# motordriver-v3_1_A3931.net
KiCad netlist of a schematic drawn in Altium Designer
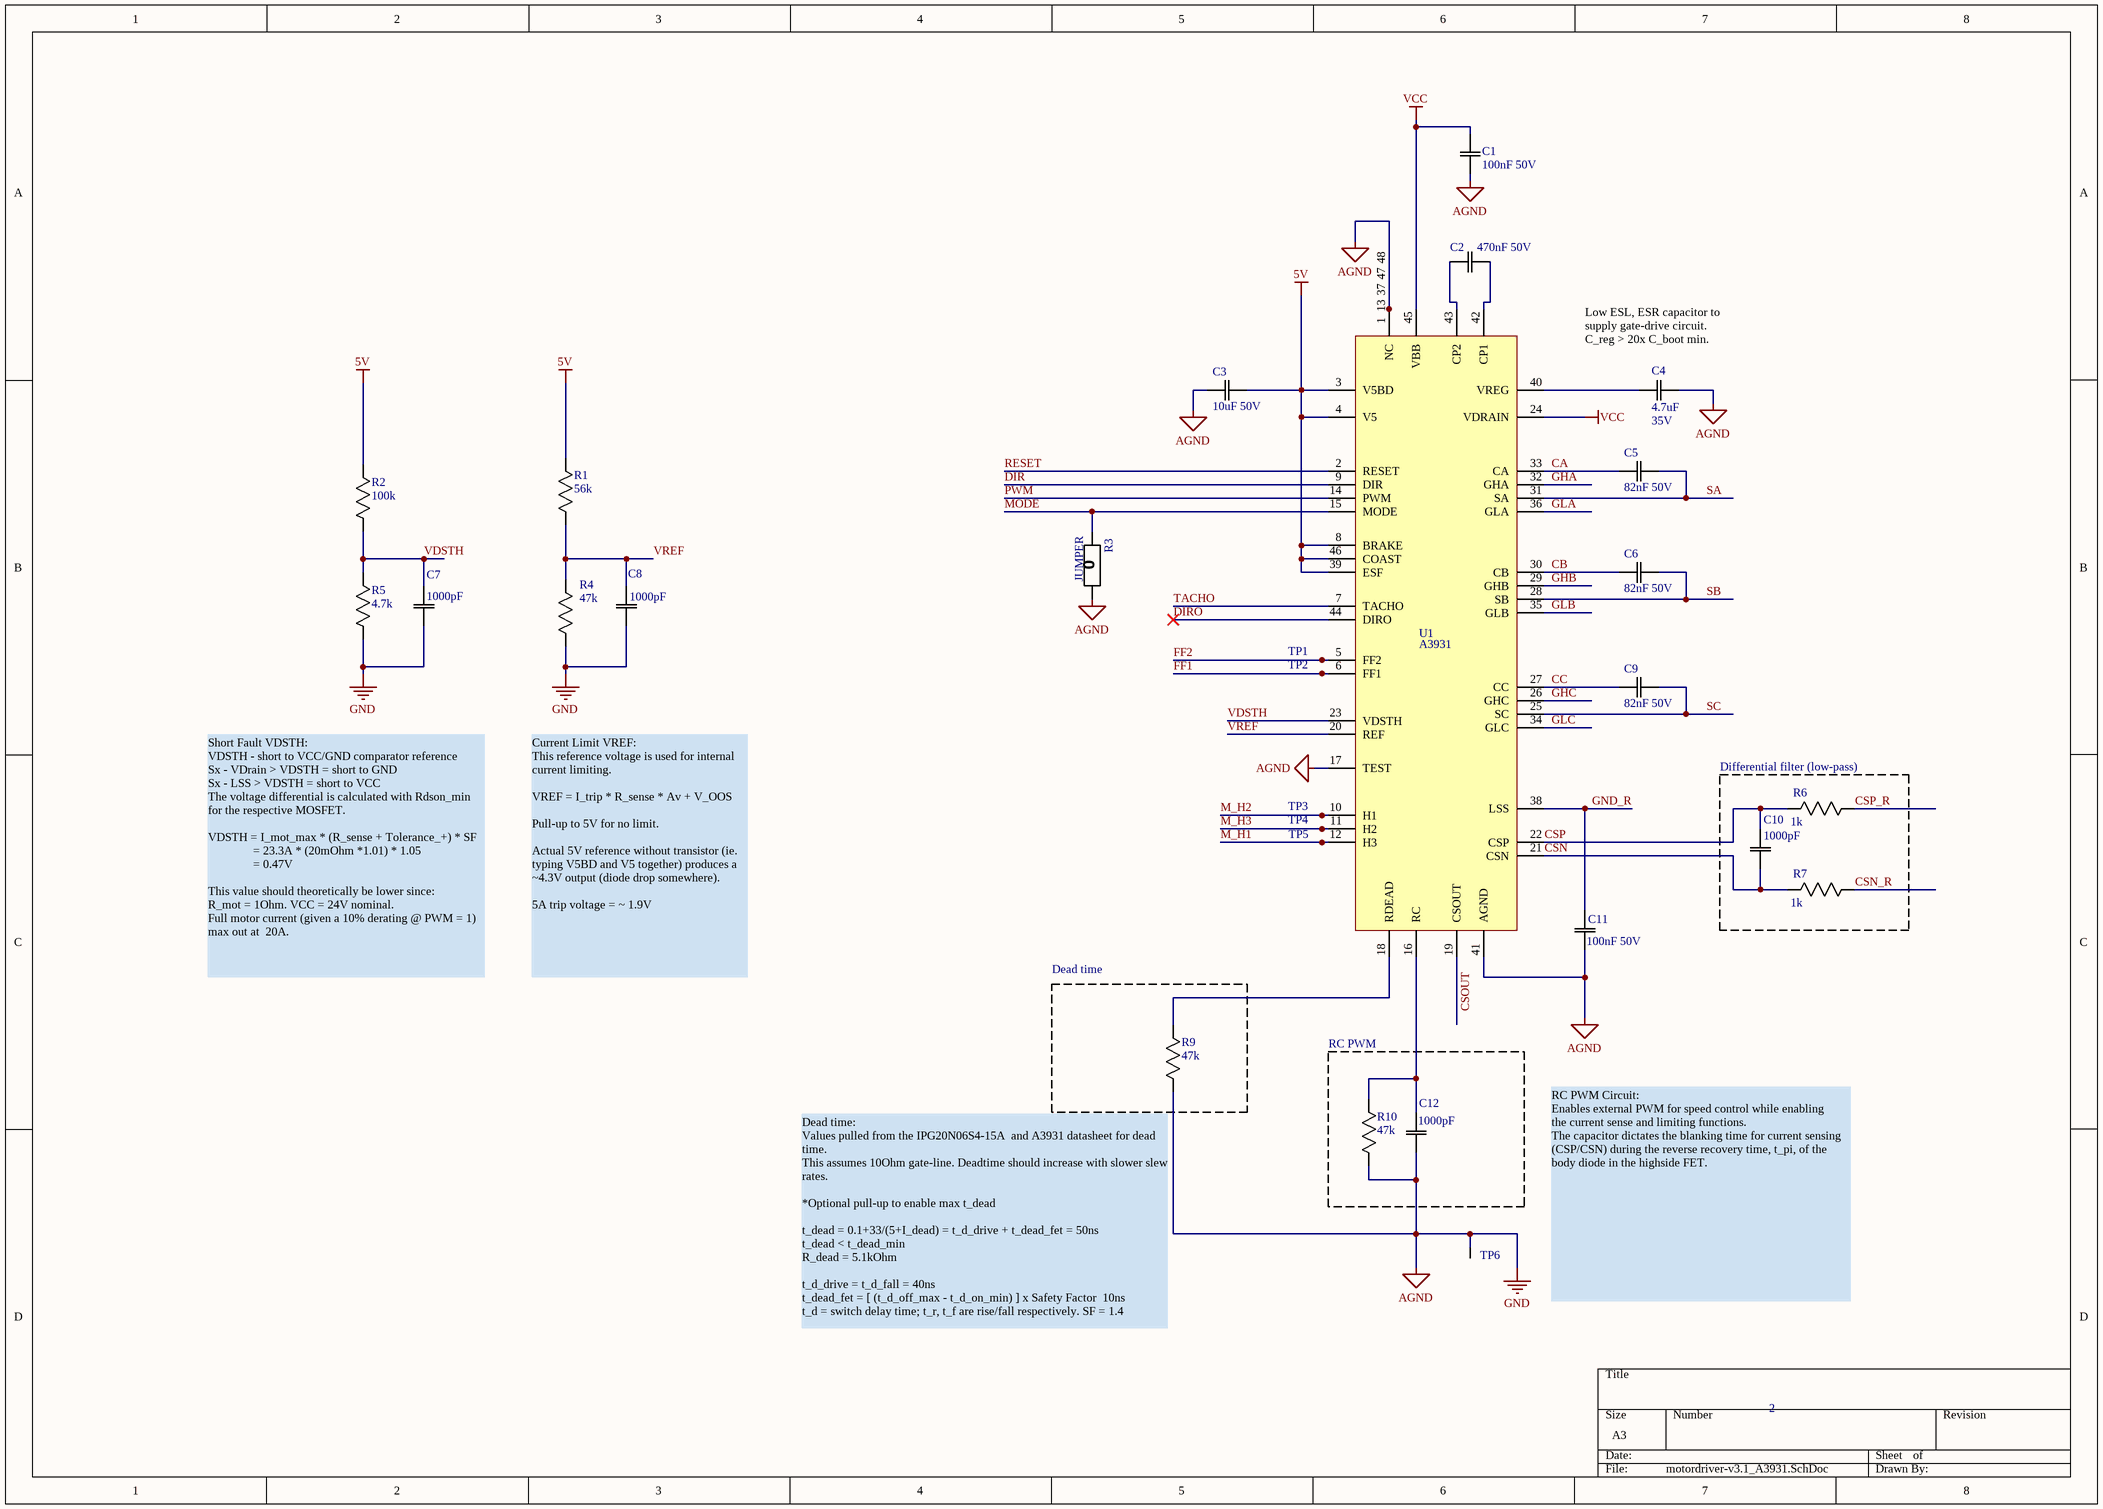
[diagram p0: motordriver-v3.1_A3931.SchDoc]

(export (version "E")
  (design (tool "Eeschema 10.0.6"))
  (components
    (comp (ref "C1")
      (value "100nF 50V")
      (footprint "0603")
      (description "CAP CER 0.1UF 50V X7R 0805")
      (fields (field (name "TOLERANCE") "10%"))
      (libsource (lib "AltiumLibraries") (part "CAP 100nF 50V"))
    )
    (comp (ref "C2")
      (value "470nF 50V")
      (footprint "0603")
      (description "CAP CER 0.1UF 50V X7R 0805")
      (fields (field (name "TOLERANCE") "10%"))
      (libsource (lib "AltiumLibraries") (part "CAP 470nF 50V"))
    )
    (comp (ref "C3")
      (value "10uF 50V")
      (footprint "0805")
      (description "CAP CER 10UF 50V X7R")
      (fields (field (name "TOLERANCE") "10%"))
      (libsource (lib "AltiumLibraries") (part "CAP 10uF 50V"))
    )
    (comp (ref "C4")
      (value "4.7uF")
      (footprint "0603")
      (description "CAP CER 4.7UF 35V X7R 0603/0805")
      (fields (field (name "TOLERANCE") "10%") (field (name "RATING") "35V"))
      (libsource (lib "AltiumLibraries") (part "CAP 4.7uF 35V"))
    )
    (comp (ref "C5")
      (value "82nF 50V")
      (footprint "0603")
      (description "CAP CER 0.082UF 50V X7R 0805")
      (fields (field (name "TOLERANCE") "5%"))
      (libsource (lib "AltiumLibraries") (part "CAP 82nF 50V"))
    )
    (comp (ref "C6")
      (value "82nF 50V")
      (footprint "0603")
      (description "CAP CER 0.082UF 50V X7R 0805")
      (fields (field (name "TOLERANCE") "5%"))
      (libsource (lib "AltiumLibraries") (part "CAP 82nF 50V"))
    )
    (comp (ref "C7")
      (value "1000pF")
      (footprint "0603")
      (description "CAP CER 1000PF 50V X7R 0603/0805")
      (fields (field (name "TOLERANCE") "10%"))
      (libsource (lib "AltiumLibraries") (part "CAP 1000pF 50V"))
    )
    (comp (ref "C8")
      (value "1000pF")
      (footprint "0603")
      (description "CAP CER 1000PF 50V X7R 0603/0805")
      (fields (field (name "TOLERANCE") "10%"))
      (libsource (lib "AltiumLibraries") (part "CAP 1000pF 50V"))
    )
    (comp (ref "C9")
      (value "82nF 50V")
      (footprint "0603")
      (description "CAP CER 0.082UF 50V X7R 0805")
      (fields (field (name "TOLERANCE") "5%"))
      (libsource (lib "AltiumLibraries") (part "CAP 82nF 50V"))
    )
    (comp (ref "C10")
      (value "1000pF")
      (footprint "0603")
      (description "CAP CER 1000PF 50V X7R 0603/0805")
      (fields (field (name "TOLERANCE") "10%"))
      (libsource (lib "AltiumLibraries") (part "CAP 1000pF 50V"))
    )
    (comp (ref "C11")
      (value "100nF 50V")
      (footprint "0603")
      (description "CAP CER 0.1UF 50V X7R 0805")
      (fields (field (name "TOLERANCE") "10%"))
      (libsource (lib "AltiumLibraries") (part "CAP 100nF 50V"))
    )
    (comp (ref "C12")
      (value "1000pF")
      (footprint "0603")
      (description "CAP CER 1000PF 50V X7R 0603/0805")
      (fields (field (name "TOLERANCE") "10%"))
      (libsource (lib "AltiumLibraries") (part "CAP 1000pF 50V"))
    )
    (comp (ref "R1")
      (value "56k")
      (footprint "0603")
      (description "RES SMD 100K OHM 1% 1/8W 0805")
      (fields (field (name "TOLERANCE") "1%"))
      (libsource (lib "") (part "RES 100k 1/8W - 1%_1"))
    )
    (comp (ref "R2")
      (value "100k")
      (footprint "0603")
      (description "RES SMD 100K OHM 1% 1/8W 0805")
      (fields (field (name "TOLERANCE") "1%"))
      (libsource (lib "AltiumLibraries") (part "RES 100k 1/8W - 1%"))
    )
    (comp (ref "R3")
      (value "JUMPER")
      (footprint "0603")
      (description "RES SMD 0 OHM JUMPER GENERIC 0805")
      (libsource (lib "AltiumLibraries") (part "RES 0 JUMPER"))
    )
    (comp (ref "R4")
      (value "47k")
      (footprint "0603")
      (description "RES SMD 47K OHM 1% 1/8W 0805")
      (fields (field (name "TOLERANCE") "1%"))
      (libsource (lib "AltiumLibraries") (part "RES 47k 1/8W - 1%"))
    )
    (comp (ref "R5")
      (value "4.7k")
      (footprint "0603")
      (description "RES SMD 4.7k OHM 1% 1/8W 0805")
      (fields (field (name "TOLERANCE") "1%"))
      (libsource (lib "AltiumLibraries") (part "RES 4.7k 1/8W - 1%"))
    )
    (comp (ref "R6")
      (value "1k")
      (footprint "0603")
      (description "RES SMD 1K OHM 5% 1/8W 0805")
      (fields (field (name "TOLERANCE") "5%"))
      (libsource (lib "AltiumLibraries") (part "RES 1k 1/8W"))
    )
    (comp (ref "R7")
      (value "1k")
      (footprint "0603")
      (description "RES SMD 1K OHM 5% 1/8W 0805")
      (fields (field (name "TOLERANCE") "5%"))
      (libsource (lib "AltiumLibraries") (part "RES 1k 1/8W"))
    )
    (comp (ref "R9")
      (value "47k")
      (footprint "0603")
      (description "RES SMD 5.1K OHM 1% 1/8W 0805")
      (fields (field (name "TOLERANCE") "1%"))
      (libsource (lib "AltiumLibraries") (part "RES 5.1k 1/8W - 1%"))
    )
    (comp (ref "R10")
      (value "47k")
      (footprint "0603")
      (description "RES SMD 47K OHM 1% 1/8W 0805")
      (fields (field (name "TOLERANCE") "1%"))
      (libsource (lib "") (part "RES 47k 1/8W - 1%_1"))
    )
    (comp (ref "TP1")
      (value "Test Point (Via)")
      (footprint "TP")
      (libsource (lib "AltiumLibraries") (part "Test Point (Via)"))
    )
    (comp (ref "TP2")
      (value "Test Point (Via)")
      (footprint "TP")
      (libsource (lib "AltiumLibraries") (part "Test Point (Via)"))
    )
    (comp (ref "TP3")
      (value "Test Point (Via)")
      (footprint "TP")
      (libsource (lib "AltiumLibraries") (part "Test Point (Via)"))
    )
    (comp (ref "TP4")
      (value "Test Point (Via)")
      (footprint "TP")
      (libsource (lib "AltiumLibraries") (part "Test Point (Via)"))
    )
    (comp (ref "TP5")
      (value "Test Point (Via)")
      (footprint "TP")
      (libsource (lib "AltiumLibraries") (part "Test Point (Via)"))
    )
    (comp (ref "TP6")
      (value "Test Point (Via)")
      (footprint "TP")
      (libsource (lib "AltiumLibraries") (part "Test Point (Via)"))
    )
    (comp (ref "U1")
      (value "A3931")
      (footprint "48-LQFP-EP (7x7)")
      (description "IC MOTOR DRIVER 5.5V-50V 48LQFP - Alternative Symbol")
      (libsource (lib "AltiumLibraries") (part "A3931_A1"))
    )
  )
  (nets
    (net (code "1") (name "/CA") (class "Default")
      (node (ref "C5") (pin "1") (pinfunction "C1_1") (pintype "passive"))
      (node (ref "U1") (pin "33") (pinfunction "CA_33") (pintype "passive"))
    )
    (net (code "2") (name "/CB") (class "Default")
      (node (ref "C6") (pin "1") (pinfunction "C1_1") (pintype "passive"))
      (node (ref "U1") (pin "30") (pinfunction "CB_30") (pintype "passive"))
    )
    (net (code "3") (name "/CC") (class "Default")
      (node (ref "C9") (pin "1") (pinfunction "C1_1") (pintype "passive"))
      (node (ref "U1") (pin "27") (pinfunction "CC_27") (pintype "passive"))
    )
    (net (code "4") (name "/CSN") (class "Default")
      (node (ref "C10") (pin "1") (pinfunction "C1_1") (pintype "passive"))
      (node (ref "R7") (pin "2") (pinfunction "R2_2") (pintype "passive"))
      (node (ref "U1") (pin "21") (pinfunction "CSN_21") (pintype "passive"))
    )
    (net (code "5") (name "/CSN_R") (class "Default")
      (node (ref "R7") (pin "1") (pinfunction "R1_1") (pintype "passive"))
    )
    (net (code "6") (name "/CSOUT") (class "Default")
      (node (ref "U1") (pin "19") (pinfunction "CSOUT_19") (pintype "passive"))
    )
    (net (code "7") (name "/CSP") (class "Default")
      (node (ref "C10") (pin "2") (pinfunction "C2_2") (pintype "passive"))
      (node (ref "R6") (pin "2") (pinfunction "R2_2") (pintype "passive"))
      (node (ref "U1") (pin "22") (pinfunction "CSP_22") (pintype "passive"))
    )
    (net (code "8") (name "/CSP_R") (class "Default")
      (node (ref "R6") (pin "1") (pinfunction "R1_1") (pintype "passive"))
    )
    (net (code "9") (name "/DIR") (class "Default")
      (node (ref "U1") (pin "9") (pinfunction "DIR_9") (pintype "passive"))
    )
    (net (code "10") (name "/DIRO") (class "Default")
      (node (ref "U1") (pin "44") (pinfunction "DIRO_44") (pintype "passive+no_connect"))
    )
    (net (code "11") (name "/FF1") (class "Default")
      (node (ref "TP2") (pin "1") (pinfunction "1_1") (pintype "passive"))
      (node (ref "U1") (pin "6") (pinfunction "FF1_6") (pintype "passive"))
    )
    (net (code "12") (name "/FF2") (class "Default")
      (node (ref "TP1") (pin "1") (pinfunction "1_1") (pintype "passive"))
      (node (ref "U1") (pin "5") (pinfunction "FF2_5") (pintype "passive"))
    )
    (net (code "13") (name "/GHA") (class "Default")
      (node (ref "U1") (pin "32") (pinfunction "GHA_32") (pintype "passive"))
    )
    (net (code "14") (name "/GHB") (class "Default")
      (node (ref "U1") (pin "29") (pinfunction "GHB_29") (pintype "passive"))
    )
    (net (code "15") (name "/GHC") (class "Default")
      (node (ref "U1") (pin "26") (pinfunction "GHC_26") (pintype "passive"))
    )
    (net (code "16") (name "/GLA") (class "Default")
      (node (ref "U1") (pin "36") (pinfunction "GLA_36") (pintype "passive"))
    )
    (net (code "17") (name "/GLB") (class "Default")
      (node (ref "U1") (pin "35") (pinfunction "GLB_35") (pintype "passive"))
    )
    (net (code "18") (name "/GLC") (class "Default")
      (node (ref "U1") (pin "34") (pinfunction "GLC_34") (pintype "passive"))
    )
    (net (code "19") (name "/GND_R") (class "Default")
      (node (ref "C11") (pin "2") (pinfunction "C2_2") (pintype "passive"))
      (node (ref "U1") (pin "38") (pinfunction "LSS_38") (pintype "passive"))
    )
    (net (code "20") (name "/MODE") (class "Default")
      (node (ref "R3") (pin "2") (pinfunction "R2_2") (pintype "passive"))
      (node (ref "U1") (pin "15") (pinfunction "MODE_15") (pintype "passive"))
    )
    (net (code "21") (name "/M_H1") (class "Default")
      (node (ref "TP5") (pin "1") (pinfunction "1_1") (pintype "passive"))
      (node (ref "U1") (pin "12") (pinfunction "H3_12") (pintype "passive"))
    )
    (net (code "22") (name "/M_H2") (class "Default")
      (node (ref "TP3") (pin "1") (pinfunction "1_1") (pintype "passive"))
      (node (ref "U1") (pin "10") (pinfunction "H1_10") (pintype "passive"))
    )
    (net (code "23") (name "/M_H3") (class "Default")
      (node (ref "TP4") (pin "1") (pinfunction "1_1") (pintype "passive"))
      (node (ref "U1") (pin "11") (pinfunction "H2_11") (pintype "passive"))
    )
    (net (code "24") (name "/PWM") (class "Default")
      (node (ref "U1") (pin "14") (pinfunction "PWM_14") (pintype "passive"))
    )
    (net (code "25") (name "/RESET") (class "Default")
      (node (ref "U1") (pin "2") (pinfunction "RESET_2") (pintype "passive"))
    )
    (net (code "26") (name "/SA") (class "Default")
      (node (ref "C5") (pin "2") (pinfunction "C2_2") (pintype "passive"))
      (node (ref "U1") (pin "31") (pinfunction "SA_31") (pintype "passive"))
    )
    (net (code "27") (name "/SB") (class "Default")
      (node (ref "C6") (pin "2") (pinfunction "C2_2") (pintype "passive"))
      (node (ref "U1") (pin "28") (pinfunction "SB_28") (pintype "passive"))
    )
    (net (code "28") (name "/SC") (class "Default")
      (node (ref "C9") (pin "2") (pinfunction "C2_2") (pintype "passive"))
      (node (ref "U1") (pin "25") (pinfunction "SC_25") (pintype "passive"))
    )
    (net (code "29") (name "/TACHO") (class "Default")
      (node (ref "U1") (pin "7") (pinfunction "TACHO_7") (pintype "passive"))
    )
    (net (code "30") (name "/VDSTH") (class "Default")
      (node (ref "C7") (pin "2") (pinfunction "C2_2") (pintype "passive"))
      (node (ref "R2") (pin "2") (pinfunction "R2_2") (pintype "passive"))
      (node (ref "R5") (pin "1") (pinfunction "R1_1") (pintype "passive"))
      (node (ref "U1") (pin "23") (pinfunction "VDSTH_23") (pintype "passive"))
    )
    (net (code "31") (name "/VREF") (class "Default")
      (node (ref "C8") (pin "2") (pinfunction "C2_2") (pintype "passive"))
      (node (ref "R1") (pin "2") (pinfunction "R2_2") (pintype "passive"))
      (node (ref "R4") (pin "2") (pinfunction "R2_2") (pintype "passive"))
      (node (ref "U1") (pin "20") (pinfunction "REF_20") (pintype "passive"))
    )
    (net (code "32") (name "5V") (class "Default")
      (node (ref "C3") (pin "2") (pinfunction "C2_2") (pintype "passive"))
      (node (ref "R1") (pin "1") (pinfunction "R1_1") (pintype "passive"))
      (node (ref "R2") (pin "1") (pinfunction "R1_1") (pintype "passive"))
      (node (ref "U1") (pin "3") (pinfunction "V5BD_3") (pintype "passive"))
      (node (ref "U1") (pin "39") (pinfunction "ESF_39") (pintype "passive"))
      (node (ref "U1") (pin "4") (pinfunction "V5_4") (pintype "passive"))
      (node (ref "U1") (pin "46") (pinfunction "COAST_46") (pintype "passive"))
      (node (ref "U1") (pin "8") (pinfunction "BRAKE_8") (pintype "passive"))
    )
    (net (code "33") (name "AGND") (class "Default")
      (node (ref "C1") (pin "1") (pinfunction "C1_1") (pintype "passive"))
      (node (ref "C11") (pin "1") (pinfunction "C1_1") (pintype "passive"))
      (node (ref "C12") (pin "1") (pinfunction "C1_1") (pintype "passive"))
      (node (ref "C3") (pin "1") (pinfunction "C1_1") (pintype "passive"))
      (node (ref "C4") (pin "2") (pinfunction "C2_2") (pintype "passive"))
      (node (ref "C7") (pin "1") (pinfunction "C1_1") (pintype "passive"))
      (node (ref "C8") (pin "1") (pinfunction "C1_1") (pintype "passive"))
      (node (ref "R10") (pin "2") (pinfunction "R2_2") (pintype "passive"))
      (node (ref "R3") (pin "1") (pinfunction "R1_1") (pintype "passive"))
      (node (ref "R4") (pin "1") (pinfunction "R1_1") (pintype "passive"))
      (node (ref "R5") (pin "2") (pinfunction "R2_2") (pintype "passive"))
      (node (ref "R9") (pin "2") (pinfunction "R2_2") (pintype "passive"))
      (node (ref "TP6") (pin "1") (pinfunction "1_1") (pintype "passive"))
      (node (ref "U1") (pin "1") (pinfunction "NC_1") (pintype "passive"))
      (node (ref "U1") (pin "13") (pinfunction "13_13") (pintype "passive"))
      (node (ref "U1") (pin "17") (pinfunction "TEST_17") (pintype "passive"))
      (node (ref "U1") (pin "37") (pinfunction "NC_37") (pintype "passive"))
      (node (ref "U1") (pin "41") (pinfunction "AGND_41") (pintype "passive"))
      (node (ref "U1") (pin "47") (pinfunction "NC_47") (pintype "passive"))
      (node (ref "U1") (pin "48") (pinfunction "NC_48") (pintype "passive"))
    )
    (net (code "34") (name "Net-(C2-C1)") (class "Default")
      (node (ref "C2") (pin "1") (pinfunction "C1_1") (pintype "passive"))
      (node (ref "U1") (pin "43") (pinfunction "CP2_43") (pintype "passive"))
    )
    (net (code "35") (name "Net-(C2-C2)") (class "Default")
      (node (ref "C2") (pin "2") (pinfunction "C2_2") (pintype "passive"))
      (node (ref "U1") (pin "42") (pinfunction "CP1_42") (pintype "passive"))
    )
    (net (code "36") (name "Net-(C4-C1)") (class "Default")
      (node (ref "C4") (pin "1") (pinfunction "C1_1") (pintype "passive"))
      (node (ref "U1") (pin "40") (pinfunction "VREG_40") (pintype "passive"))
    )
    (net (code "37") (name "Net-(C12-C2)") (class "Default")
      (node (ref "C12") (pin "2") (pinfunction "C2_2") (pintype "passive"))
      (node (ref "R10") (pin "1") (pinfunction "R1_1") (pintype "passive"))
      (node (ref "U1") (pin "16") (pinfunction "RC_16") (pintype "passive"))
    )
    (net (code "38") (name "Net-(R9-R1)") (class "Default")
      (node (ref "R9") (pin "1") (pinfunction "R1_1") (pintype "passive"))
      (node (ref "U1") (pin "18") (pinfunction "RDEAD_18") (pintype "passive"))
    )
    (net (code "39") (name "VCC") (class "Default")
      (node (ref "C1") (pin "2") (pinfunction "C2_2") (pintype "passive"))
      (node (ref "U1") (pin "24") (pinfunction "VDRAIN_24") (pintype "passive"))
      (node (ref "U1") (pin "45") (pinfunction "VBB_45") (pintype "passive"))
    )
  )
)
